# PCB_Design.net
KiCad netlist of a schematic drawn in EasyEDA
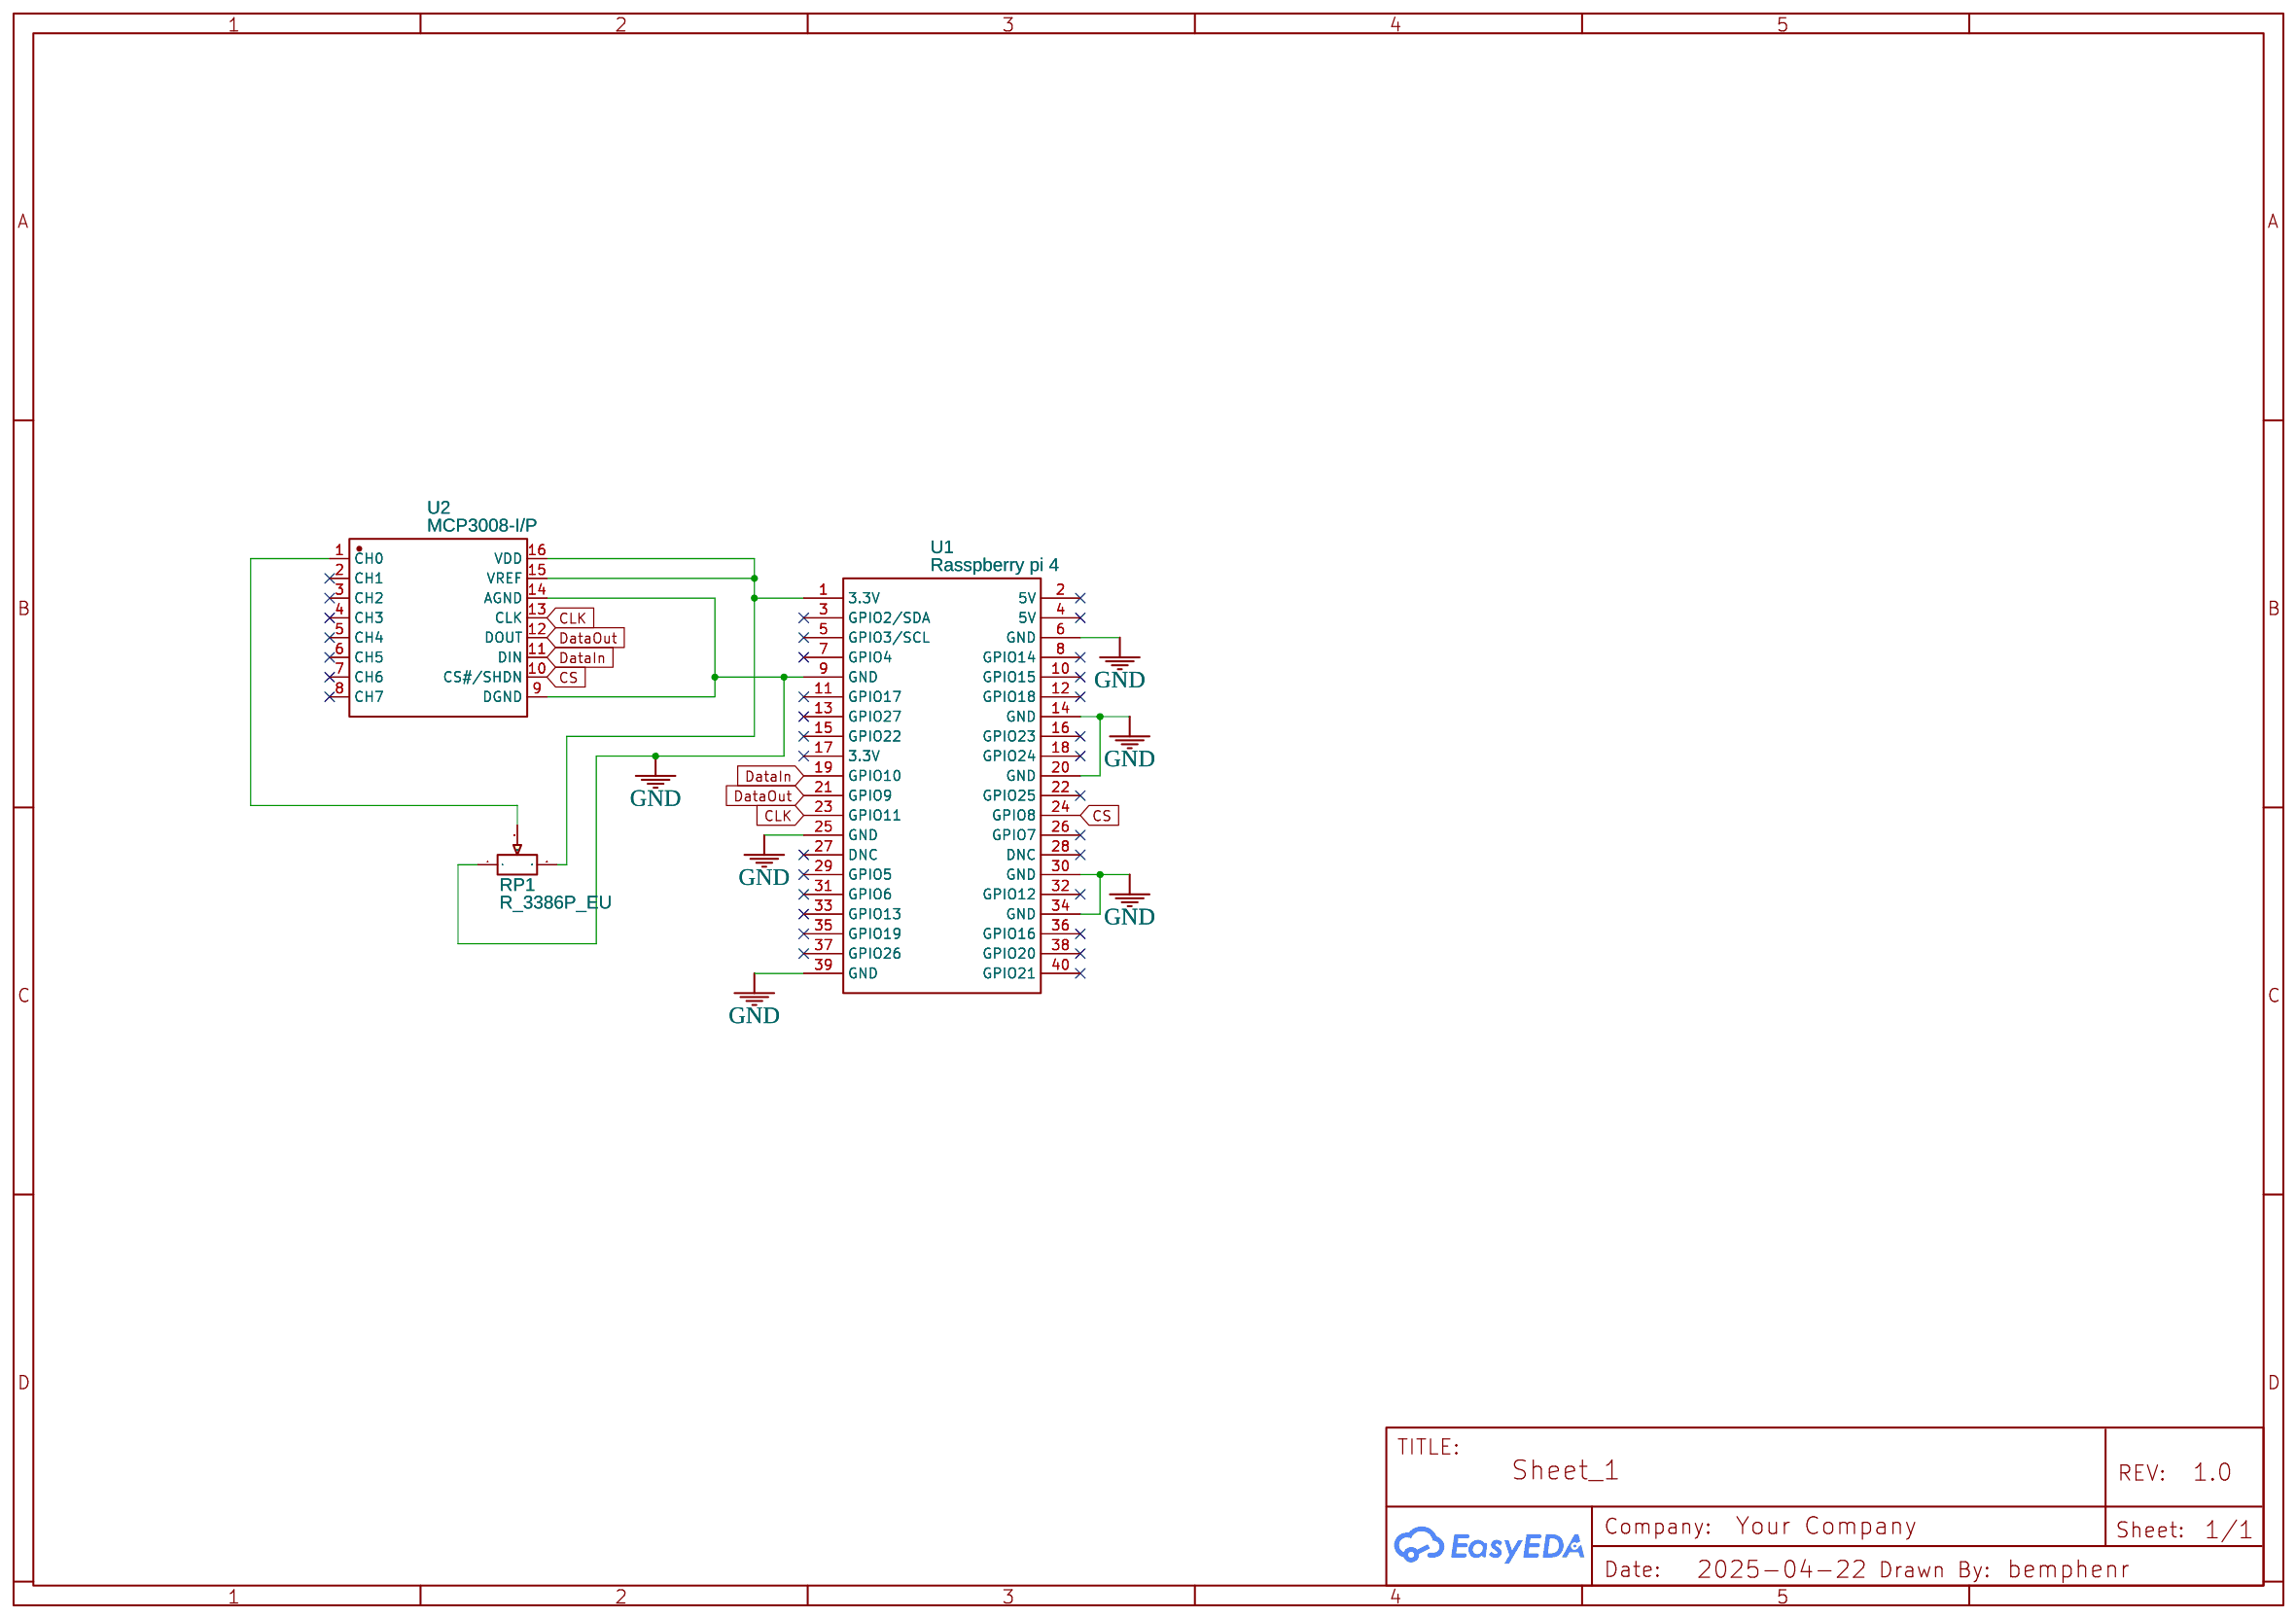
[diagram p0: schematic sheet]

(export (version "E")
  (design (tool "Eeschema 10.0.6"))
  (components
    (comp (ref "RP1") (value "R_3386P_EU") (libsource (lib "") (part "R_3386P_EU")))
    (comp (ref "U1") (value "Rasspberry pi 4") (libsource (lib "") (part "Rasspberry pi 4")))
    (comp (ref "U2")
      (value "MCP3008-I/P")
      (fields (field (name "Manufacturer") "MICROCHIP(美国微芯)"))
      (libsource (lib "") (part "MCP3008-I/P"))
    )
  )
  (nets
    (net (code "1") (name "CLK") (class "Default")
      (node (ref "U1") (pin "23") (pinfunction "GPIO11_23") (pintype "bidirectional"))
      (node (ref "U2") (pin "13") (pinfunction "CLK_13") (pintype "unspecified"))
    )
    (net (code "2") (name "CS") (class "Default")
      (node (ref "U1") (pin "24") (pinfunction "GPIO8_24") (pintype "bidirectional"))
      (node (ref "U2") (pin "10") (pinfunction "CS#/SHDN_10") (pintype "unspecified"))
    )
    (net (code "3") (name "DataIn") (class "Default")
      (node (ref "U1") (pin "19") (pinfunction "GPIO10_19") (pintype "bidirectional"))
      (node (ref "U2") (pin "11") (pinfunction "DIN_11") (pintype "unspecified"))
    )
    (net (code "4") (name "DataOut") (class "Default")
      (node (ref "U1") (pin "21") (pinfunction "GPIO9_21") (pintype "bidirectional"))
      (node (ref "U2") (pin "12") (pinfunction "DOUT_12") (pintype "unspecified"))
    )
    (net (code "5") (name "GND") (class "Default")
      (node (ref "RP1") (pin "1") (pinfunction "1_1") (pintype "input"))
      (node (ref "U1") (pin "14") (pinfunction "GND_14") (pintype "unspecified"))
      (node (ref "U1") (pin "20") (pinfunction "GND_20") (pintype "unspecified"))
      (node (ref "U1") (pin "25") (pinfunction "GND_25") (pintype "unspecified"))
      (node (ref "U1") (pin "30") (pinfunction "GND_30") (pintype "unspecified"))
      (node (ref "U1") (pin "34") (pinfunction "GND_34") (pintype "unspecified"))
      (node (ref "U1") (pin "39") (pinfunction "GND_39") (pintype "unspecified"))
      (node (ref "U1") (pin "6") (pinfunction "GND_6") (pintype "unspecified"))
      (node (ref "U1") (pin "9") (pinfunction "GND_9") (pintype "unspecified"))
      (node (ref "U2") (pin "14") (pinfunction "AGND_14") (pintype "unspecified"))
      (node (ref "U2") (pin "9") (pinfunction "DGND_9") (pintype "unspecified"))
    )
    (net (code "6") (name "Net-(U2-CH0)") (class "Default")
      (node (ref "RP1") (pin "2") (pinfunction "2_2") (pintype "input"))
      (node (ref "U2") (pin "1") (pinfunction "CH0_1") (pintype "unspecified"))
    )
    (net (code "7") (name "Net-(U2-VDD)") (class "Default")
      (node (ref "RP1") (pin "3") (pinfunction "3_3") (pintype "input"))
      (node (ref "U1") (pin "1") (pinfunction "3.3V_1") (pintype "passive"))
      (node (ref "U2") (pin "15") (pinfunction "VREF_15") (pintype "unspecified"))
      (node (ref "U2") (pin "16") (pinfunction "VDD_16") (pintype "unspecified"))
    )
    (net (code "8") (name "unconnected-(U1-3.3V-Pad17)") (class "Default")
      (node (ref "U1") (pin "17") (pinfunction "3.3V_17") (pintype "passive+no_connect"))
    )
    (net (code "9") (name "unconnected-(U1-5V-Pad2)") (class "Default")
      (node (ref "U1") (pin "2") (pinfunction "5V_2") (pintype "passive+no_connect"))
    )
    (net (code "10") (name "unconnected-(U1-5V-Pad4)") (class "Default")
      (node (ref "U1") (pin "4") (pinfunction "5V_4") (pintype "passive+no_connect"))
    )
    (net (code "11") (name "unconnected-(U1-DNC-Pad27)") (class "Default")
      (node (ref "U1") (pin "27") (pinfunction "DNC_27") (pintype "unspecified+no_connect"))
    )
    (net (code "12") (name "unconnected-(U1-DNC-Pad28)") (class "Default")
      (node (ref "U1") (pin "28") (pinfunction "DNC_28") (pintype "unspecified+no_connect"))
    )
    (net (code "13") (name "unconnected-(U1-GPIO2{slash}SDA-Pad3)") (class "Default")
      (node (ref "U1") (pin "3") (pinfunction "GPIO2/SDA_3") (pintype "bidirectional+no_connect"))
    )
    (net (code "14") (name "unconnected-(U1-GPIO3{slash}SCL-Pad5)") (class "Default")
      (node (ref "U1") (pin "5") (pinfunction "GPIO3/SCL_5") (pintype "bidirectional+no_connect"))
    )
    (net (code "15") (name "unconnected-(U1-GPIO4-Pad7)") (class "Default")
      (node (ref "U1") (pin "7") (pinfunction "GPIO4_7") (pintype "bidirectional+no_connect"))
    )
    (net (code "16") (name "unconnected-(U1-GPIO5-Pad29)") (class "Default")
      (node (ref "U1") (pin "29") (pinfunction "GPIO5_29") (pintype "bidirectional+no_connect"))
    )
    (net (code "17") (name "unconnected-(U1-GPIO6-Pad31)") (class "Default")
      (node (ref "U1") (pin "31") (pinfunction "GPIO6_31") (pintype "bidirectional+no_connect"))
    )
    (net (code "18") (name "unconnected-(U1-GPIO7-Pad26)") (class "Default")
      (node (ref "U1") (pin "26") (pinfunction "GPIO7_26") (pintype "bidirectional+no_connect"))
    )
    (net (code "19") (name "unconnected-(U1-GPIO12-Pad32)") (class "Default")
      (node (ref "U1") (pin "32") (pinfunction "GPIO12_32") (pintype "bidirectional+no_connect"))
    )
    (net (code "20") (name "unconnected-(U1-GPIO13-Pad33)") (class "Default")
      (node (ref "U1") (pin "33") (pinfunction "GPIO13_33") (pintype "bidirectional+no_connect"))
    )
    (net (code "21") (name "unconnected-(U1-GPIO14-Pad8)") (class "Default")
      (node (ref "U1") (pin "8") (pinfunction "GPIO14_8") (pintype "bidirectional+no_connect"))
    )
    (net (code "22") (name "unconnected-(U1-GPIO15-Pad10)") (class "Default")
      (node (ref "U1") (pin "10") (pinfunction "GPIO15_10") (pintype "bidirectional+no_connect"))
    )
    (net (code "23") (name "unconnected-(U1-GPIO16-Pad36)") (class "Default")
      (node (ref "U1") (pin "36") (pinfunction "GPIO16_36") (pintype "bidirectional+no_connect"))
    )
    (net (code "24") (name "unconnected-(U1-GPIO17-Pad11)") (class "Default")
      (node (ref "U1") (pin "11") (pinfunction "GPIO17_11") (pintype "bidirectional+no_connect"))
    )
    (net (code "25") (name "unconnected-(U1-GPIO18-Pad12)") (class "Default")
      (node (ref "U1") (pin "12") (pinfunction "GPIO18_12") (pintype "bidirectional+no_connect"))
    )
    (net (code "26") (name "unconnected-(U1-GPIO19-Pad35)") (class "Default")
      (node (ref "U1") (pin "35") (pinfunction "GPIO19_35") (pintype "bidirectional+no_connect"))
    )
    (net (code "27") (name "unconnected-(U1-GPIO20-Pad38)") (class "Default")
      (node (ref "U1") (pin "38") (pinfunction "GPIO20_38") (pintype "bidirectional+no_connect"))
    )
    (net (code "28") (name "unconnected-(U1-GPIO21-Pad40)") (class "Default")
      (node (ref "U1") (pin "40") (pinfunction "GPIO21_40") (pintype "bidirectional+no_connect"))
    )
    (net (code "29") (name "unconnected-(U1-GPIO22-Pad15)") (class "Default")
      (node (ref "U1") (pin "15") (pinfunction "GPIO22_15") (pintype "bidirectional+no_connect"))
    )
    (net (code "30") (name "unconnected-(U1-GPIO23-Pad16)") (class "Default")
      (node (ref "U1") (pin "16") (pinfunction "GPIO23_16") (pintype "bidirectional+no_connect"))
    )
    (net (code "31") (name "unconnected-(U1-GPIO24-Pad18)") (class "Default")
      (node (ref "U1") (pin "18") (pinfunction "GPIO24_18") (pintype "bidirectional+no_connect"))
    )
    (net (code "32") (name "unconnected-(U1-GPIO25-Pad22)") (class "Default")
      (node (ref "U1") (pin "22") (pinfunction "GPIO25_22") (pintype "bidirectional+no_connect"))
    )
    (net (code "33") (name "unconnected-(U1-GPIO26-Pad37)") (class "Default")
      (node (ref "U1") (pin "37") (pinfunction "GPIO26_37") (pintype "bidirectional+no_connect"))
    )
    (net (code "34") (name "unconnected-(U1-GPIO27-Pad13)") (class "Default")
      (node (ref "U1") (pin "13") (pinfunction "GPIO27_13") (pintype "bidirectional+no_connect"))
    )
    (net (code "35") (name "unconnected-(U2-CH1-Pad2)") (class "Default")
      (node (ref "U2") (pin "2") (pinfunction "CH1_2") (pintype "unspecified+no_connect"))
    )
    (net (code "36") (name "unconnected-(U2-CH2-Pad3)") (class "Default")
      (node (ref "U2") (pin "3") (pinfunction "CH2_3") (pintype "unspecified+no_connect"))
    )
    (net (code "37") (name "unconnected-(U2-CH3-Pad4)") (class "Default")
      (node (ref "U2") (pin "4") (pinfunction "CH3_4") (pintype "unspecified+no_connect"))
    )
    (net (code "38") (name "unconnected-(U2-CH4-Pad5)") (class "Default")
      (node (ref "U2") (pin "5") (pinfunction "CH4_5") (pintype "unspecified+no_connect"))
    )
    (net (code "39") (name "unconnected-(U2-CH5-Pad6)") (class "Default")
      (node (ref "U2") (pin "6") (pinfunction "CH5_6") (pintype "unspecified+no_connect"))
    )
    (net (code "40") (name "unconnected-(U2-CH6-Pad7)") (class "Default")
      (node (ref "U2") (pin "7") (pinfunction "CH6_7") (pintype "unspecified+no_connect"))
    )
    (net (code "41") (name "unconnected-(U2-CH7-Pad8)") (class "Default")
      (node (ref "U2") (pin "8") (pinfunction "CH7_8") (pintype "unspecified+no_connect"))
    )
  )
)
